# PSU2.net
KiCad netlist of a schematic drawn in Altium Designer
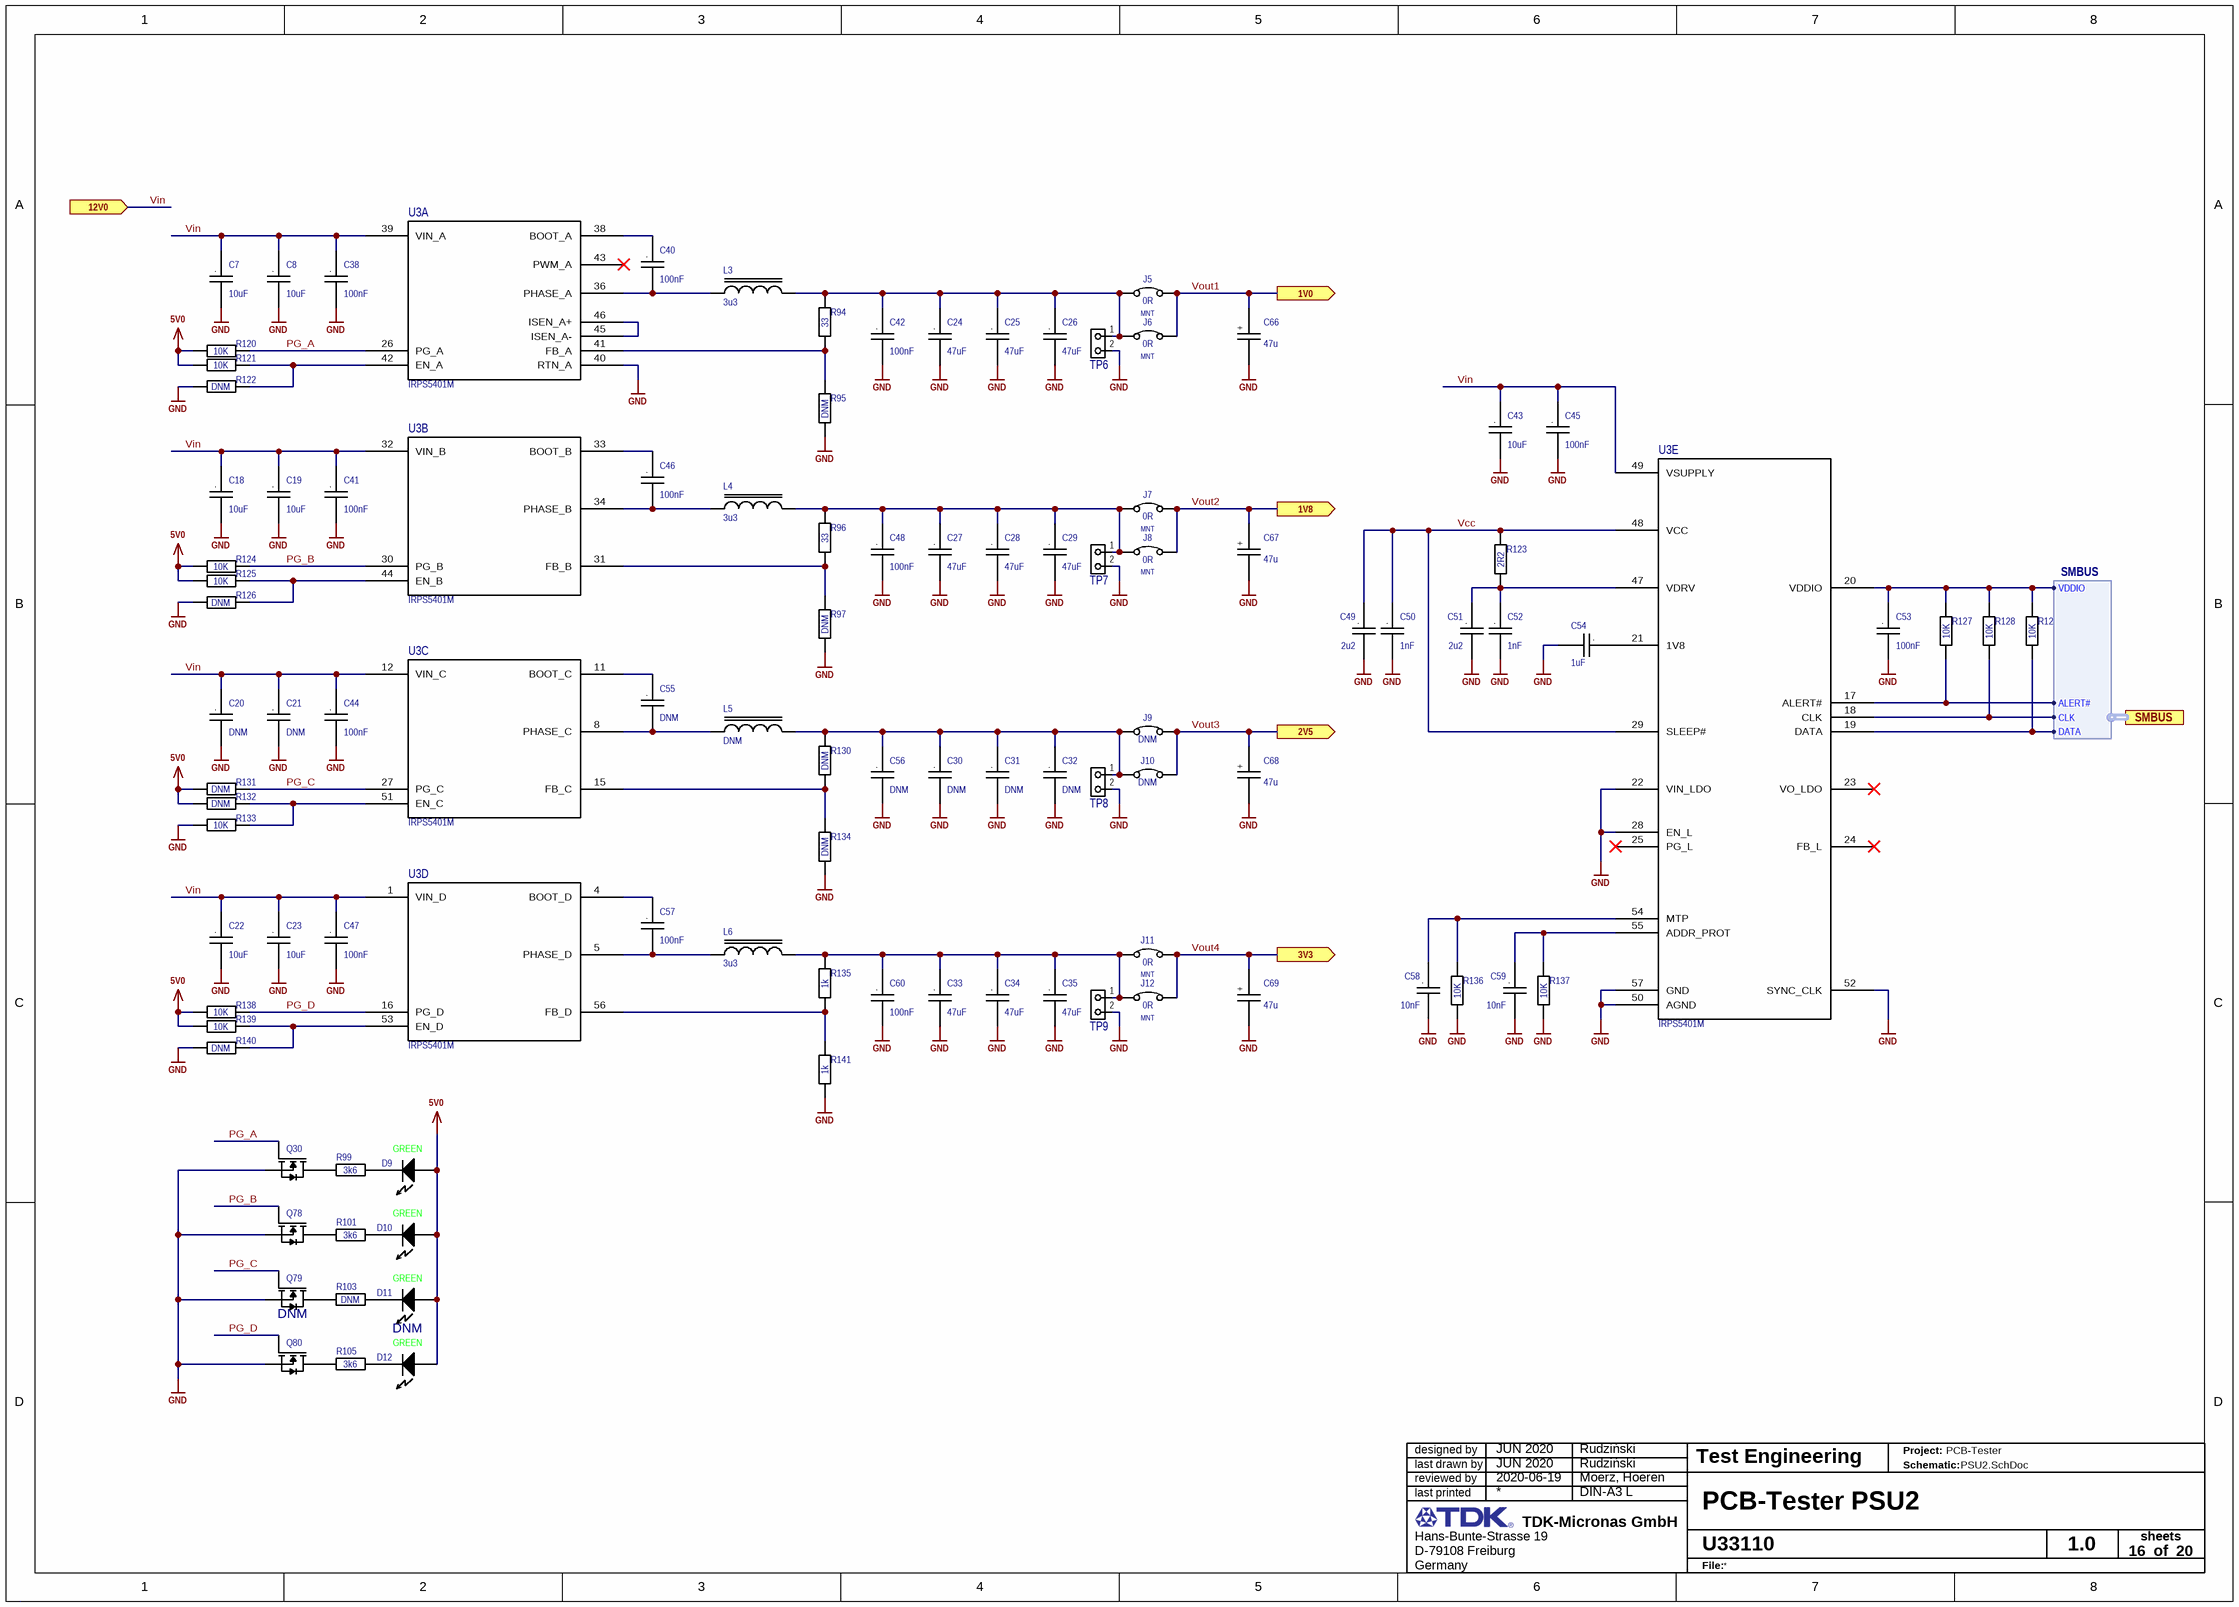
[diagram p0: PSU2.SchDoc]

(export (version "E")
  (design (tool "Eeschema 10.0.6"))
  (components
    (comp (ref "C7")
      (value "10uF")
      (footprint "C1206 Reflow")
      (description "CAP CER 10UF 25V X7R 1206")
      (fields (field (name "TOLERANCE") "±10%") (field (name "02. DISTRIBUTOR PART NUMBER") "445-7705-6-ND"))
      (libsource (lib "chickenfood") (part "C"))
    )
    (comp (ref "C8")
      (value "10uF")
      (footprint "C1206 Reflow")
      (description "CAP CER 10UF 25V X7R 1206")
      (fields (field (name "TOLERANCE") "±10%") (field (name "02. DISTRIBUTOR PART NUMBER") "445-7705-6-ND"))
      (libsource (lib "chickenfood") (part "C"))
    )
    (comp (ref "C18")
      (value "10uF")
      (footprint "C1206 Reflow")
      (description "CAP CER 10UF 25V X7R 1206")
      (fields (field (name "TOLERANCE") "±10%") (field (name "02. DISTRIBUTOR PART NUMBER") "445-7705-6-ND"))
      (libsource (lib "chickenfood") (part "C"))
    )
    (comp (ref "C19")
      (value "10uF")
      (footprint "C1206 Reflow")
      (description "CAP CER 10UF 25V X7R 1206")
      (fields (field (name "TOLERANCE") "±10%") (field (name "02. DISTRIBUTOR PART NUMBER") "445-7705-6-ND"))
      (libsource (lib "chickenfood") (part "C"))
    )
    (comp (ref "C20")
      (value "DNM")
      (footprint "C1206 Reflow")
      (description "CAP CER 10UF 25V X7R 1206")
      (fields (field (name "TOLERANCE") "±10%") (field (name "02. DISTRIBUTOR PART NUMBER") "445-7705-6-ND"))
      (libsource (lib "chickenfood") (part "C"))
    )
    (comp (ref "C21")
      (value "DNM")
      (footprint "C1206 Reflow")
      (description "CAP CER 10UF 25V X7R 1206")
      (fields (field (name "TOLERANCE") "±10%") (field (name "02. DISTRIBUTOR PART NUMBER") "445-7705-6-ND"))
      (libsource (lib "chickenfood") (part "C"))
    )
    (comp (ref "C22")
      (value "10uF")
      (footprint "C1206 Reflow")
      (description "CAP CER 10UF 25V X7R 1206")
      (fields (field (name "TOLERANCE") "±10%") (field (name "02. DISTRIBUTOR PART NUMBER") "445-7705-6-ND"))
      (libsource (lib "chickenfood") (part "C"))
    )
    (comp (ref "C23")
      (value "10uF")
      (footprint "C1206 Reflow")
      (description "CAP CER 10UF 25V X7R 1206")
      (fields (field (name "TOLERANCE") "±10%") (field (name "02. DISTRIBUTOR PART NUMBER") "445-7705-6-ND"))
      (libsource (lib "chickenfood") (part "C"))
    )
    (comp (ref "C24")
      (value "47uF")
      (footprint "C1210 Reflow")
      (description "CAP CER 47UF 10V X5R 1210")
      (fields (field (name "TOLERANCE") "±20%") (field (name "02. DISTRIBUTOR PART NUMBER") "1276-3380-6-ND"))
      (libsource (lib "chickenfood") (part "C"))
    )
    (comp (ref "C25")
      (value "47uF")
      (footprint "C1210 Reflow")
      (description "CAP CER 47UF 10V X5R 1210")
      (fields (field (name "TOLERANCE") "±20%") (field (name "02. DISTRIBUTOR PART NUMBER") "1276-3380-6-ND"))
      (libsource (lib "chickenfood") (part "C"))
    )
    (comp (ref "C26")
      (value "47uF")
      (footprint "C1210 Reflow")
      (description "CAP CER 47UF 10V X5R 1210")
      (fields (field (name "TOLERANCE") "±20%") (field (name "02. DISTRIBUTOR PART NUMBER") "1276-3380-6-ND"))
      (libsource (lib "chickenfood") (part "C"))
    )
    (comp (ref "C27")
      (value "47uF")
      (footprint "C1210 Reflow")
      (description "CAP CER 47UF 10V X5R 1210")
      (fields (field (name "TOLERANCE") "±20%") (field (name "02. DISTRIBUTOR PART NUMBER") "1276-3380-6-ND"))
      (libsource (lib "chickenfood") (part "C"))
    )
    (comp (ref "C28")
      (value "47uF")
      (footprint "C1210 Reflow")
      (description "CAP CER 47UF 10V X5R 1210")
      (fields (field (name "TOLERANCE") "±20%") (field (name "02. DISTRIBUTOR PART NUMBER") "1276-3380-6-ND"))
      (libsource (lib "chickenfood") (part "C"))
    )
    (comp (ref "C29")
      (value "47uF")
      (footprint "C1210 Reflow")
      (description "CAP CER 47UF 10V X5R 1210")
      (fields (field (name "TOLERANCE") "±20%") (field (name "02. DISTRIBUTOR PART NUMBER") "1276-3380-6-ND"))
      (libsource (lib "chickenfood") (part "C"))
    )
    (comp (ref "C30")
      (value "DNM")
      (footprint "C1210 Reflow")
      (description "CAP CER 47UF 10V X5R 1210")
      (fields (field (name "TOLERANCE") "±20%") (field (name "02. DISTRIBUTOR PART NUMBER") "1276-3380-6-ND"))
      (libsource (lib "chickenfood") (part "C"))
    )
    (comp (ref "C31")
      (value "DNM")
      (footprint "C1210 Reflow")
      (description "CAP CER 47UF 10V X5R 1210")
      (fields (field (name "TOLERANCE") "±20%") (field (name "02. DISTRIBUTOR PART NUMBER") "1276-3380-6-ND"))
      (libsource (lib "chickenfood") (part "C"))
    )
    (comp (ref "C32")
      (value "DNM")
      (footprint "C1210 Reflow")
      (description "CAP CER 47UF 10V X5R 1210")
      (fields (field (name "TOLERANCE") "±20%") (field (name "02. DISTRIBUTOR PART NUMBER") "1276-3380-6-ND"))
      (libsource (lib "chickenfood") (part "C"))
    )
    (comp (ref "C33")
      (value "47uF")
      (footprint "C1210 Reflow")
      (description "CAP CER 47UF 10V X5R 1210")
      (fields (field (name "TOLERANCE") "±20%") (field (name "02. DISTRIBUTOR PART NUMBER") "1276-3380-6-ND"))
      (libsource (lib "chickenfood") (part "C"))
    )
    (comp (ref "C34")
      (value "47uF")
      (footprint "C1210 Reflow")
      (description "CAP CER 47UF 10V X5R 1210")
      (fields (field (name "TOLERANCE") "±20%") (field (name "02. DISTRIBUTOR PART NUMBER") "1276-3380-6-ND"))
      (libsource (lib "chickenfood") (part "C"))
    )
    (comp (ref "C35")
      (value "47uF")
      (footprint "C1210 Reflow")
      (description "CAP CER 47UF 10V X5R 1210")
      (fields (field (name "TOLERANCE") "±20%") (field (name "02. DISTRIBUTOR PART NUMBER") "1276-3380-6-ND"))
      (libsource (lib "chickenfood") (part "C"))
    )
    (comp (ref "C38")
      (value "100nF")
      (footprint "C0402 Reflow")
      (description "CAP CER 0.1UF 25V X7R 0402")
      (fields (field (name "TOLERANCE") "±10%") (field (name "02. DISTRIBUTOR PART NUMBER") "311-2077-6-ND"))
      (libsource (lib "chickenfood") (part "C"))
    )
    (comp (ref "C40")
      (value "100nF")
      (footprint "C0402 Reflow")
      (description "CAP CER 0.1UF 25V X7R 0402")
      (fields (field (name "TOLERANCE") "±10%") (field (name "02. DISTRIBUTOR PART NUMBER") "311-2077-6-ND"))
      (libsource (lib "chickenfood") (part "C"))
    )
    (comp (ref "C41")
      (value "100nF")
      (footprint "C0402 Reflow")
      (description "CAP CER 0.1UF 25V X7R 0402")
      (fields (field (name "TOLERANCE") "±10%") (field (name "02. DISTRIBUTOR PART NUMBER") "311-2077-6-ND"))
      (libsource (lib "chickenfood") (part "C"))
    )
    (comp (ref "C42")
      (value "100nF")
      (footprint "C0402 Reflow")
      (description "CAP CER 0.1UF 25V X7R 0402")
      (fields (field (name "TOLERANCE") "±10%") (field (name "02. DISTRIBUTOR PART NUMBER") "311-2077-6-ND"))
      (libsource (lib "chickenfood") (part "C"))
    )
    (comp (ref "C43")
      (value "10uF")
      (footprint "C1206 Reflow")
      (description "CAP CER 10UF 25V X7R 1206")
      (fields (field (name "TOLERANCE") "±10%") (field (name "02. DISTRIBUTOR PART NUMBER") "445-7705-6-ND"))
      (libsource (lib "chickenfood") (part "C"))
    )
    (comp (ref "C44")
      (value "100nF")
      (footprint "C0402 Reflow")
      (description "CAP CER 0.1UF 25V X7R 0402")
      (fields (field (name "TOLERANCE") "±10%") (field (name "02. DISTRIBUTOR PART NUMBER") "311-2077-6-ND"))
      (libsource (lib "chickenfood") (part "C"))
    )
    (comp (ref "C45")
      (value "100nF")
      (footprint "C0402 Reflow")
      (description "CAP CER 0.1UF 25V X7R 0402")
      (fields (field (name "TOLERANCE") "±10%") (field (name "02. DISTRIBUTOR PART NUMBER") "311-2077-6-ND"))
      (libsource (lib "chickenfood") (part "C"))
    )
    (comp (ref "C46")
      (value "100nF")
      (footprint "C0402 Reflow")
      (description "CAP CER 0.1UF 25V X7R 0402")
      (fields (field (name "TOLERANCE") "±10%") (field (name "02. DISTRIBUTOR PART NUMBER") "311-2077-6-ND"))
      (libsource (lib "chickenfood") (part "C"))
    )
    (comp (ref "C47")
      (value "100nF")
      (footprint "C0402 Reflow")
      (description "CAP CER 0.1UF 25V X7R 0402")
      (fields (field (name "TOLERANCE") "±10%") (field (name "02. DISTRIBUTOR PART NUMBER") "311-2077-6-ND"))
      (libsource (lib "chickenfood") (part "C"))
    )
    (comp (ref "C48")
      (value "100nF")
      (footprint "C0402 Reflow")
      (description "CAP CER 0.1UF 25V X7R 0402")
      (fields (field (name "TOLERANCE") "±10%") (field (name "02. DISTRIBUTOR PART NUMBER") "311-2077-6-ND"))
      (libsource (lib "chickenfood") (part "C"))
    )
    (comp (ref "C49")
      (value "2u2")
      (footprint "C0805 Reflow")
      (description "CAP CER 2.2UF 10V X7R 0805")
      (fields
        (field (name "02. DISTRIBUTOR PART NUMBER") "1276-1188-1-ND")
        (field (name "07. MANUFACTURER  PART NUMBER") "CL21B225KPFNNNE")
      )
      (libsource (lib "PCB-Tester-Board-V1") (part "C_11"))
    )
    (comp (ref "C50")
      (value "1nF")
      (footprint "C0402 Reflow")
      (description "CAP CER 1000PF 25V X7R 0402")
      (fields (field (name "TOLERANCE") "±10%") (field (name "02. DISTRIBUTOR PART NUMBER") "399-1031-6-ND"))
      (libsource (lib "PCB-Tester-Board-V1") (part "C_7"))
    )
    (comp (ref "C51")
      (value "2u2")
      (footprint "C0805 Reflow")
      (description "CAP CER 2.2UF 10V X7R 0805")
      (fields
        (field (name "02. DISTRIBUTOR PART NUMBER") "1276-1188-1-ND")
        (field (name "07. MANUFACTURER  PART NUMBER") "CL21B225KPFNNNE")
      )
      (libsource (lib "PCB-Tester-Board-V1") (part "C_11"))
    )
    (comp (ref "C52")
      (value "1nF")
      (footprint "C0402 Reflow")
      (description "CAP CER 1000PF 25V X7R 0402")
      (fields (field (name "TOLERANCE") "±10%") (field (name "02. DISTRIBUTOR PART NUMBER") "399-1031-6-ND"))
      (libsource (lib "PCB-Tester-Board-V1") (part "C_7"))
    )
    (comp (ref "C53")
      (value "100nF")
      (footprint "C0402 Reflow")
      (description "CAP CER 0.1UF 25V X7R 0402")
      (fields (field (name "TOLERANCE") "±10%") (field (name "02. DISTRIBUTOR PART NUMBER") "311-2077-6-ND"))
      (libsource (lib "chickenfood") (part "C"))
    )
    (comp (ref "C54")
      (value "1uF")
      (footprint "C0402 Reflow")
      (description "CAP CER 1UF 6.3V X7R 0402")
      (fields (field (name "TOLERANCE") "±10%") (field (name "02. DISTRIBUTOR PART NUMBER") "490-13339-6-ND"))
      (libsource (lib "PCB-Tester-Board-V1") (part "C_2"))
    )
    (comp (ref "C55")
      (value "DNM")
      (footprint "C0402 Reflow")
      (description "CAP CER 0.1UF 25V X7R 0402")
      (fields (field (name "TOLERANCE") "±10%") (field (name "02. DISTRIBUTOR PART NUMBER") "311-2077-6-ND"))
      (libsource (lib "chickenfood") (part "C"))
    )
    (comp (ref "C56")
      (value "DNM")
      (footprint "C0402 Reflow")
      (description "CAP CER 0.1UF 25V X7R 0402")
      (fields (field (name "TOLERANCE") "±10%") (field (name "02. DISTRIBUTOR PART NUMBER") "311-2077-6-ND"))
      (libsource (lib "chickenfood") (part "C"))
    )
    (comp (ref "C57")
      (value "100nF")
      (footprint "C0402 Reflow")
      (description "CAP CER 0.1UF 25V X7R 0402")
      (fields (field (name "TOLERANCE") "±10%") (field (name "02. DISTRIBUTOR PART NUMBER") "311-2077-6-ND"))
      (libsource (lib "chickenfood") (part "C"))
    )
    (comp (ref "C58")
      (value "10nF")
      (footprint "C0402 Reflow")
      (description "CAP CER 0.01UF 25V X7R 0402")
      (fields (field (name "TOLERANCE") "±10%") (field (name "02. DISTRIBUTOR PART NUMBER") "490-6043-1-ND"))
      (libsource (lib "PCB-Tester-Board-V1") (part "C_10"))
    )
    (comp (ref "C59")
      (value "10nF")
      (footprint "C0402 Reflow")
      (description "CAP CER 0.01UF 25V X7R 0402")
      (fields (field (name "TOLERANCE") "±10%") (field (name "02. DISTRIBUTOR PART NUMBER") "490-6043-1-ND"))
      (libsource (lib "PCB-Tester-Board-V1") (part "C_10"))
    )
    (comp (ref "C60")
      (value "100nF")
      (footprint "C0402 Reflow")
      (description "CAP CER 0.1UF 25V X7R 0402")
      (fields (field (name "TOLERANCE") "±10%") (field (name "02. DISTRIBUTOR PART NUMBER") "311-2077-6-ND"))
      (libsource (lib "chickenfood") (part "C"))
    )
    (comp (ref "C66")
      (value "47u")
      (footprint "CAP_TAN_B")
      (description "CAP TANT 47UF 20% 10V 1411")
      (fields
        (field (name "02. DISTRIBUTOR PART NUMBER") "478-12531-1-ND")
        (field (name "07. MANUFACTURER  PART NUMBER") "F971A476MBAHT3")
      )
      (libsource (lib "PCB-Tester-Board-V1") (part "C+_TAN"))
    )
    (comp (ref "C67")
      (value "47u")
      (footprint "CAP_TAN_B")
      (description "CAP TANT 47UF 20% 10V 1411")
      (fields
        (field (name "02. DISTRIBUTOR PART NUMBER") "478-12531-1-ND")
        (field (name "07. MANUFACTURER  PART NUMBER") "F971A476MBAHT3")
      )
      (libsource (lib "PCB-Tester-Board-V1") (part "C+_TAN"))
    )
    (comp (ref "C68")
      (value "47u")
      (footprint "CAP_TAN_B")
      (description "CAP TANT 47UF 20% 10V 1411")
      (fields
        (field (name "02. DISTRIBUTOR PART NUMBER") "478-12531-1-ND")
        (field (name "07. MANUFACTURER  PART NUMBER") "F971A476MBAHT3")
      )
      (libsource (lib "PCB-Tester-Board-V1") (part "C+_TAN"))
    )
    (comp (ref "C69")
      (value "47u")
      (footprint "CAP_TAN_B")
      (description "CAP TANT 47UF 20% 10V 1411")
      (fields
        (field (name "02. DISTRIBUTOR PART NUMBER") "478-12531-1-ND")
        (field (name "07. MANUFACTURER  PART NUMBER") "F971A476MBAHT3")
      )
      (libsource (lib "PCB-Tester-Board-V1") (part "C+_TAN"))
    )
    (comp (ref "D9")
      (value "D")
      (footprint "L0603G")
      (description "LED GREEN DIFFUSED 0603 SMD")
      (fields
        (field (name "02. DISTRIBUTOR PART NUMBER") "475-2709-6-ND")
        (field (name "07. MANUFACTURER  PART NUMBER") "LG L29K-G2J1-24-Z")
        (field (name "COLOR") "GREEN")
      )
      (libsource (lib "chickenfood") (part "LED"))
    )
    (comp (ref "D10")
      (value "D")
      (footprint "L0603G")
      (description "LED GREEN DIFFUSED 0603 SMD")
      (fields
        (field (name "02. DISTRIBUTOR PART NUMBER") "475-2709-6-ND")
        (field (name "07. MANUFACTURER  PART NUMBER") "LG L29K-G2J1-24-Z")
        (field (name "COLOR") "GREEN")
      )
      (libsource (lib "chickenfood") (part "LED"))
    )
    (comp (ref "D11")
      (value "D")
      (footprint "L0603G")
      (description "LED GREEN DIFFUSED 0603 SMD")
      (fields
        (field (name "02. DISTRIBUTOR PART NUMBER") "475-2709-6-ND")
        (field (name "07. MANUFACTURER  PART NUMBER") "LG L29K-G2J1-24-Z")
        (field (name "COLOR") "GREEN")
        (field (name "NICNAME") "DNM")
      )
      (libsource (lib "chickenfood") (part "LED"))
    )
    (comp (ref "D12")
      (value "D")
      (footprint "L0603G")
      (description "LED GREEN DIFFUSED 0603 SMD")
      (fields
        (field (name "02. DISTRIBUTOR PART NUMBER") "475-2709-6-ND")
        (field (name "07. MANUFACTURER  PART NUMBER") "LG L29K-G2J1-24-Z")
        (field (name "COLOR") "GREEN")
      )
      (libsource (lib "chickenfood") (part "LED"))
    )
    (comp (ref "J5")
      (value "0R")
      (footprint "JumperSMD")
      (description "RES SMD 0 OHM JUMPER 1/10W 0603")
      (fields
        (field (name "02. DISTRIBUTOR PART NUMBER") "311-0.0GRDKR-ND")
        (field (name "07. MANUFACTURER  PART NUMBER") "RC0603JR-070RL")
        (field (name "POPULATED") "MNT")
      )
      (libsource (lib "chickenfood") (part "Jumper SMD"))
    )
    (comp (ref "J6")
      (value "0R")
      (footprint "JumperSMD")
      (description "RES SMD 0 OHM JUMPER 1/10W 0603")
      (fields
        (field (name "02. DISTRIBUTOR PART NUMBER") "311-0.0GRDKR-ND")
        (field (name "07. MANUFACTURER  PART NUMBER") "RC0603JR-070RL")
        (field (name "POPULATED") "MNT")
      )
      (libsource (lib "chickenfood") (part "Jumper SMD"))
    )
    (comp (ref "J7")
      (value "0R")
      (footprint "JumperSMD")
      (description "RES SMD 0 OHM JUMPER 1/10W 0603")
      (fields
        (field (name "02. DISTRIBUTOR PART NUMBER") "311-0.0GRDKR-ND")
        (field (name "07. MANUFACTURER  PART NUMBER") "RC0603JR-070RL")
        (field (name "POPULATED") "MNT")
      )
      (libsource (lib "chickenfood") (part "Jumper SMD"))
    )
    (comp (ref "J8")
      (value "0R")
      (footprint "JumperSMD")
      (description "RES SMD 0 OHM JUMPER 1/10W 0603")
      (fields
        (field (name "02. DISTRIBUTOR PART NUMBER") "311-0.0GRDKR-ND")
        (field (name "07. MANUFACTURER  PART NUMBER") "RC0603JR-070RL")
        (field (name "POPULATED") "MNT")
      )
      (libsource (lib "chickenfood") (part "Jumper SMD"))
    )
    (comp (ref "J9")
      (value "DNM")
      (footprint "JumperSMD")
      (description "RES SMD 0 OHM JUMPER 1/10W 0603")
      (fields
        (field (name "02. DISTRIBUTOR PART NUMBER") "311-0.0GRDKR-ND")
        (field (name "07. MANUFACTURER  PART NUMBER") "RC0603JR-070RL")
      )
      (libsource (lib "chickenfood") (part "Jumper SMD"))
    )
    (comp (ref "J10")
      (value "DNM")
      (footprint "JumperSMD")
      (description "RES SMD 0 OHM JUMPER 1/10W 0603")
      (fields
        (field (name "02. DISTRIBUTOR PART NUMBER") "311-0.0GRDKR-ND")
        (field (name "07. MANUFACTURER  PART NUMBER") "RC0603JR-070RL")
      )
      (libsource (lib "chickenfood") (part "Jumper SMD"))
    )
    (comp (ref "J11")
      (value "0R")
      (footprint "JumperSMD")
      (description "RES SMD 0 OHM JUMPER 1/10W 0603")
      (fields
        (field (name "02. DISTRIBUTOR PART NUMBER") "311-0.0GRDKR-ND")
        (field (name "07. MANUFACTURER  PART NUMBER") "RC0603JR-070RL")
        (field (name "POPULATED") "MNT")
      )
      (libsource (lib "chickenfood") (part "Jumper SMD"))
    )
    (comp (ref "J12")
      (value "0R")
      (footprint "JumperSMD")
      (description "RES SMD 0 OHM JUMPER 1/10W 0603")
      (fields
        (field (name "02. DISTRIBUTOR PART NUMBER") "311-0.0GRDKR-ND")
        (field (name "07. MANUFACTURER  PART NUMBER") "RC0603JR-070RL")
        (field (name "POPULATED") "MNT")
      )
      (libsource (lib "chickenfood") (part "Jumper SMD"))
    )
    (comp (ref "L3")
      (value "L")
      (footprint "XAL7070")
      (description "Fixed Inductors 3.3uH Shld 20% 15.1A 9.42mOhms AECQ2")
      (fields
        (field (name "02. DISTRIBUTOR PART NUMBER") "994-XAL7070-332MEC")
        (field (name "07. MANUFACTURER  PART NUMBER") "XAL7070-332MEC")
        (field (name "INDUCTANCE") "3u3")
      )
      (libsource (lib "PCB-Tester-Board-V1") (part "INDUCTOR"))
    )
    (comp (ref "L4")
      (value "L")
      (footprint "XAL7070")
      (description "Fixed Inductors 3.3uH Shld 20% 15.1A 9.42mOhms AECQ2")
      (fields
        (field (name "02. DISTRIBUTOR PART NUMBER") "994-XAL7070-332MEC")
        (field (name "07. MANUFACTURER  PART NUMBER") "XAL7070-332MEC")
        (field (name "INDUCTANCE") "3u3")
      )
      (libsource (lib "PCB-Tester-Board-V1") (part "INDUCTOR"))
    )
    (comp (ref "L5")
      (value "L")
      (footprint "XAL7070")
      (description "Fixed Inductors 3.3uH Shld 20% 15.1A 9.42mOhms AECQ2")
      (fields
        (field (name "02. DISTRIBUTOR PART NUMBER") "994-XAL7070-332MEC")
        (field (name "07. MANUFACTURER  PART NUMBER") "XAL7070-332MEC")
        (field (name "INDUCTANCE") "DNM")
      )
      (libsource (lib "PCB-Tester-Board-V1") (part "INDUCTOR"))
    )
    (comp (ref "L6")
      (value "L")
      (footprint "XAL7070")
      (description "Fixed Inductors 3.3uH Shld 20% 15.1A 9.42mOhms AECQ2")
      (fields
        (field (name "02. DISTRIBUTOR PART NUMBER") "994-XAL7070-332MEC")
        (field (name "07. MANUFACTURER  PART NUMBER") "XAL7070-332MEC")
        (field (name "INDUCTANCE") "3u3")
      )
      (libsource (lib "PCB-Tester-Board-V1") (part "INDUCTOR"))
    )
    (comp (ref "Q30")
      (value "Q")
      (footprint "SOT23-3")
      (description "MOSFET N-CH 25V 680MA SOT-23")
      (fields
        (field (name "02. DISTRIBUTOR PART NUMBER") "FDV303NDKR-ND")
        (field (name "07. MANUFACTURER  PART NUMBER") "FDV303N")
      )
      (libsource (lib "PCB-Tester-Board-V1") (part "FDV303N"))
    )
    (comp (ref "Q78")
      (value "Q")
      (footprint "SOT23-3")
      (description "MOSFET N-CH 25V 680MA SOT-23")
      (fields
        (field (name "02. DISTRIBUTOR PART NUMBER") "FDV303NDKR-ND")
        (field (name "07. MANUFACTURER  PART NUMBER") "FDV303N")
      )
      (libsource (lib "PCB-Tester-Board-V1") (part "FDV303N"))
    )
    (comp (ref "Q79")
      (value "Q")
      (footprint "SOT23-3")
      (description "MOSFET N-CH 25V 680MA SOT-23")
      (fields
        (field (name "02. DISTRIBUTOR PART NUMBER") "FDV303NDKR-ND")
        (field (name "07. MANUFACTURER  PART NUMBER") "FDV303N")
        (field (name "NICNAME") "DNM")
      )
      (libsource (lib "PCB-Tester-Board-V1") (part "FDV303N"))
    )
    (comp (ref "Q80")
      (value "Q")
      (footprint "SOT23-3")
      (description "MOSFET N-CH 25V 680MA SOT-23")
      (fields
        (field (name "02. DISTRIBUTOR PART NUMBER") "FDV303NDKR-ND")
        (field (name "07. MANUFACTURER  PART NUMBER") "FDV303N")
      )
      (libsource (lib "PCB-Tester-Board-V1") (part "FDV303N"))
    )
    (comp (ref "R94")
      (value "33")
      (footprint "R0402 Reflow")
      (description "RES SMD 33 OHM 1% 1/16W 0402")
      (fields
        (field (name "TOLERANCE") "±1%")
        (field (name "02. DISTRIBUTOR PART NUMBER") "311-33.0LRDKR-ND")
      )
      (libsource (lib "chickenfood") (part "R"))
    )
    (comp (ref "R95")
      (value "DNM")
      (footprint "R0402 Reflow")
      (description "RES SMD 10K OHM 1% 1/16W 0402")
      (fields
        (field (name "TOLERANCE") "±1%")
        (field (name "02. DISTRIBUTOR PART NUMBER") "311-10.0KLRDKR-ND")
      )
      (libsource (lib "chickenfood") (part "R"))
    )
    (comp (ref "R96")
      (value "33")
      (footprint "R0402 Reflow")
      (description "RES SMD 33 OHM 1% 1/16W 0402")
      (fields
        (field (name "TOLERANCE") "±1%")
        (field (name "02. DISTRIBUTOR PART NUMBER") "311-33.0LRDKR-ND")
      )
      (libsource (lib "chickenfood") (part "R"))
    )
    (comp (ref "R97")
      (value "DNM")
      (footprint "R0402 Reflow")
      (description "RES SMD 10K OHM 1% 1/16W 0402")
      (fields
        (field (name "TOLERANCE") "±1%")
        (field (name "02. DISTRIBUTOR PART NUMBER") "311-10.0KLRDKR-ND")
      )
      (libsource (lib "chickenfood") (part "R"))
    )
    (comp (ref "R99")
      (value "3k6")
      (footprint "R0603 Reflow")
      (description "RES SMD 3.6K OHM 1% 1/10W 0603")
      (fields
        (field (name "TOLERANCE") "±1%")
        (field (name "02. DISTRIBUTOR PART NUMBER") "311-3.60KHRCT-ND")
      )
      (libsource (lib "") (part "R_2"))
    )
    (comp (ref "R101")
      (value "3k6")
      (footprint "R0603 Reflow")
      (description "RES SMD 3.6K OHM 1% 1/10W 0603")
      (fields
        (field (name "TOLERANCE") "±1%")
        (field (name "02. DISTRIBUTOR PART NUMBER") "311-3.60KHRCT-ND")
      )
      (libsource (lib "") (part "R_2"))
    )
    (comp (ref "R103")
      (value "DNM")
      (footprint "R0603 Reflow")
      (description "RES SMD 1.65K OHM 1% 1/16W 0402")
      (fields (field (name "TOLERANCE") "±1%") (field (name "02. DISTRIBUTOR PART NUMBER") "YAG3043DKR-ND"))
      (libsource (lib "") (part "R_2"))
    )
    (comp (ref "R105")
      (value "3k6")
      (footprint "R0603 Reflow")
      (description "RES SMD 3.6K OHM 1% 1/10W 0603")
      (fields
        (field (name "TOLERANCE") "±1%")
        (field (name "02. DISTRIBUTOR PART NUMBER") "311-3.60KHRCT-ND")
      )
      (libsource (lib "") (part "R_2"))
    )
    (comp (ref "R120")
      (value "10K")
      (footprint "R0402 Reflow")
      (description "RES SMD 10K OHM 1% 1/16W 0402")
      (fields
        (field (name "TOLERANCE") "±1%")
        (field (name "02. DISTRIBUTOR PART NUMBER") "311-10.0KLRDKR-ND")
      )
      (libsource (lib "") (part "R_1"))
    )
    (comp (ref "R121")
      (value "10K")
      (footprint "R0402 Reflow")
      (description "RES SMD 10K OHM 1% 1/16W 0402")
      (fields
        (field (name "TOLERANCE") "±1%")
        (field (name "02. DISTRIBUTOR PART NUMBER") "311-10.0KLRDKR-ND")
      )
      (libsource (lib "") (part "R_1"))
    )
    (comp (ref "R122")
      (value "DNM")
      (footprint "R0402 Reflow")
      (description "RES SMD 10K OHM 1% 1/16W 0402")
      (fields
        (field (name "TOLERANCE") "±1%")
        (field (name "02. DISTRIBUTOR PART NUMBER") "311-10.0KLRDKR-ND")
      )
      (libsource (lib "") (part "R_1"))
    )
    (comp (ref "R123")
      (value "2R2")
      (footprint "R0402 Reflow")
      (description "RES SMD 2.2 OHM 1% 1/16W 0402")
      (fields (field (name "TOLERANCE") "±1%") (field (name "02. DISTRIBUTOR PART NUMBER") "311-2.20LRTR-ND"))
      (libsource (lib "PCB-Tester-Board-V1") (part "R_24"))
    )
    (comp (ref "R124")
      (value "10K")
      (footprint "R0402 Reflow")
      (description "RES SMD 10K OHM 1% 1/16W 0402")
      (fields
        (field (name "TOLERANCE") "±1%")
        (field (name "02. DISTRIBUTOR PART NUMBER") "311-10.0KLRDKR-ND")
      )
      (libsource (lib "") (part "R_1"))
    )
    (comp (ref "R125")
      (value "10K")
      (footprint "R0402 Reflow")
      (description "RES SMD 10K OHM 1% 1/16W 0402")
      (fields
        (field (name "TOLERANCE") "±1%")
        (field (name "02. DISTRIBUTOR PART NUMBER") "311-10.0KLRDKR-ND")
      )
      (libsource (lib "") (part "R_1"))
    )
    (comp (ref "R126")
      (value "DNM")
      (footprint "R0402 Reflow")
      (description "RES SMD 10K OHM 1% 1/16W 0402")
      (fields
        (field (name "TOLERANCE") "±1%")
        (field (name "02. DISTRIBUTOR PART NUMBER") "311-10.0KLRDKR-ND")
      )
      (libsource (lib "") (part "R_1"))
    )
    (comp (ref "R127")
      (value "10K")
      (footprint "R0402 Reflow")
      (description "RES SMD 10K OHM 1% 1/16W 0402")
      (fields
        (field (name "TOLERANCE") "±1%")
        (field (name "02. DISTRIBUTOR PART NUMBER") "311-10.0KLRDKR-ND")
      )
      (libsource (lib "chickenfood") (part "R"))
    )
    (comp (ref "R128")
      (value "10K")
      (footprint "R0402 Reflow")
      (description "RES SMD 10K OHM 1% 1/16W 0402")
      (fields
        (field (name "TOLERANCE") "±1%")
        (field (name "02. DISTRIBUTOR PART NUMBER") "311-10.0KLRDKR-ND")
      )
      (libsource (lib "chickenfood") (part "R"))
    )
    (comp (ref "R129")
      (value "10K")
      (footprint "R0402 Reflow")
      (description "RES SMD 10K OHM 1% 1/16W 0402")
      (fields
        (field (name "TOLERANCE") "±1%")
        (field (name "02. DISTRIBUTOR PART NUMBER") "311-10.0KLRDKR-ND")
      )
      (libsource (lib "chickenfood") (part "R"))
    )
    (comp (ref "R130")
      (value "DNM")
      (footprint "R0402 Reflow")
      (description "RES SMD 10K OHM 1% 1/16W 0402")
      (fields
        (field (name "TOLERANCE") "±1%")
        (field (name "02. DISTRIBUTOR PART NUMBER") "311-10.0KLRDKR-ND")
      )
      (libsource (lib "chickenfood") (part "R"))
    )
    (comp (ref "R131")
      (value "DNM")
      (footprint "R0402 Reflow")
      (description "RES SMD 10K OHM 1% 1/16W 0402")
      (fields
        (field (name "TOLERANCE") "±1%")
        (field (name "02. DISTRIBUTOR PART NUMBER") "311-10.0KLRDKR-ND")
      )
      (libsource (lib "") (part "R_1"))
    )
    (comp (ref "R132")
      (value "DNM")
      (footprint "R0402 Reflow")
      (description "RES SMD 10K OHM 1% 1/16W 0402")
      (fields
        (field (name "TOLERANCE") "±1%")
        (field (name "02. DISTRIBUTOR PART NUMBER") "311-10.0KLRDKR-ND")
      )
      (libsource (lib "") (part "R_1"))
    )
    (comp (ref "R133")
      (value "10K")
      (footprint "R0402 Reflow")
      (description "RES SMD 10K OHM 1% 1/16W 0402")
      (fields
        (field (name "TOLERANCE") "±1%")
        (field (name "02. DISTRIBUTOR PART NUMBER") "311-10.0KLRDKR-ND")
      )
      (libsource (lib "") (part "R_1"))
    )
    (comp (ref "R134")
      (value "DNM")
      (footprint "R0402 Reflow")
      (description "RES SMD 10K OHM 1% 1/16W 0402")
      (fields
        (field (name "TOLERANCE") "±1%")
        (field (name "02. DISTRIBUTOR PART NUMBER") "311-10.0KLRDKR-ND")
      )
      (libsource (lib "chickenfood") (part "R"))
    )
    (comp (ref "R135")
      (value "1k")
      (footprint "R0402 Reflow")
      (description "RES SMD 1K OHM 1% 1/16W 0402")
      (fields (field (name "TOLERANCE") "±1%") (field (name "02. DISTRIBUTOR PART NUMBER") "YAG1254CT-ND"))
      (libsource (lib "chickenfood") (part "R"))
    )
    (comp (ref "R136")
      (value "10K")
      (footprint "R0402 Reflow")
      (description "RES SMD 10K OHM 1% 1/16W 0402")
      (fields
        (field (name "TOLERANCE") "±1%")
        (field (name "02. DISTRIBUTOR PART NUMBER") "311-10.0KLRDKR-ND")
      )
      (libsource (lib "chickenfood") (part "R"))
    )
    (comp (ref "R137")
      (value "10K")
      (footprint "R0402 Reflow")
      (description "RES SMD 10K OHM 1% 1/16W 0402")
      (fields
        (field (name "TOLERANCE") "±1%")
        (field (name "02. DISTRIBUTOR PART NUMBER") "311-10.0KLRDKR-ND")
      )
      (libsource (lib "chickenfood") (part "R"))
    )
    (comp (ref "R138")
      (value "10K")
      (footprint "R0402 Reflow")
      (description "RES SMD 10K OHM 1% 1/16W 0402")
      (fields
        (field (name "TOLERANCE") "±1%")
        (field (name "02. DISTRIBUTOR PART NUMBER") "311-10.0KLRDKR-ND")
      )
      (libsource (lib "") (part "R_1"))
    )
    (comp (ref "R139")
      (value "10K")
      (footprint "R0402 Reflow")
      (description "RES SMD 10K OHM 1% 1/16W 0402")
      (fields
        (field (name "TOLERANCE") "±1%")
        (field (name "02. DISTRIBUTOR PART NUMBER") "311-10.0KLRDKR-ND")
      )
      (libsource (lib "") (part "R_1"))
    )
    (comp (ref "R140")
      (value "DNM")
      (footprint "R0402 Reflow")
      (description "RES SMD 10K OHM 1% 1/16W 0402")
      (fields
        (field (name "TOLERANCE") "±1%")
        (field (name "02. DISTRIBUTOR PART NUMBER") "311-10.0KLRDKR-ND")
      )
      (libsource (lib "") (part "R_1"))
    )
    (comp (ref "R141")
      (value "1k")
      (footprint "R0402 Reflow")
      (description "RES SMD 1K OHM 1% 1/16W 0402")
      (fields (field (name "TOLERANCE") "±1%") (field (name "02. DISTRIBUTOR PART NUMBER") "YAG1254CT-ND"))
      (libsource (lib "chickenfood") (part "R"))
    )
    (comp (ref "TP6")
      (value "TP")
      (footprint "DualTestpoint 100mils")
      (description "Dual testpoint, pitch 2.54mm")
      (fields (field (name "02. DISTRIBUTOR PART NUMBER") "HMTSW-103-07-G-S-240"))
      (libsource (lib "PCB-Tester-Board-V1") (part "DualTestpoint 100mils"))
    )
    (comp (ref "TP7")
      (value "TP")
      (footprint "DualTestpoint 100mils")
      (description "Dual testpoint, pitch 2.54mm")
      (fields (field (name "02. DISTRIBUTOR PART NUMBER") "HMTSW-103-07-G-S-240"))
      (libsource (lib "PCB-Tester-Board-V1") (part "DualTestpoint 100mils"))
    )
    (comp (ref "TP8")
      (value "TP")
      (footprint "DualTestpoint 100mils")
      (description "Dual testpoint, pitch 2.54mm")
      (fields (field (name "02. DISTRIBUTOR PART NUMBER") "HMTSW-103-07-G-S-240"))
      (libsource (lib "PCB-Tester-Board-V1") (part "DualTestpoint 100mils"))
    )
    (comp (ref "TP9")
      (value "TP")
      (footprint "DualTestpoint 100mils")
      (description "Dual testpoint, pitch 2.54mm")
      (fields (field (name "02. DISTRIBUTOR PART NUMBER") "HMTSW-103-07-G-S-240"))
      (libsource (lib "PCB-Tester-Board-V1") (part "DualTestpoint 100mils"))
    )
    (comp (ref "U3")
      (value "IRPS5401M")
      (footprint "QFN4-7x7-56_IRPS5401M")
      (description "POL - SUPIRBUCK")
      (fields
        (field (name "MFR") "Infineon")
        (field (name "07. MANUFACTURER  PART NUMBER") "IRPS5401MTRPBF")
        (field (name "NICNAME") "IRPS5401M")
      )
      (libsource (lib "PCB-Tester-Board-V1") (part "IRPS5401M"))
    )
  )
  (nets
    (net (code "2") (name "/PG_A") (class "Default")
      (node (ref "Q30") (pin "1") (pinfunction "G_1") (pintype "passive"))
      (node (ref "R120") (pin "1") (pinfunction "1_1") (pintype "passive"))
      (node (ref "U3") (pin "26") (pinfunction "PG_A_26") (pintype "passive"))
    )
    (net (code "3") (name "/PG_B") (class "Default")
      (node (ref "Q78") (pin "1") (pinfunction "G_1") (pintype "passive"))
      (node (ref "R124") (pin "1") (pinfunction "1_1") (pintype "passive"))
      (node (ref "U3") (pin "30") (pinfunction "PG_B_30") (pintype "passive"))
    )
    (net (code "4") (name "/PG_C") (class "Default")
      (node (ref "Q79") (pin "1") (pinfunction "G_1") (pintype "passive"))
      (node (ref "R131") (pin "1") (pinfunction "1_1") (pintype "passive"))
      (node (ref "U3") (pin "27") (pinfunction "PG_C_27") (pintype "passive"))
    )
    (net (code "5") (name "/PG_D") (class "Default")
      (node (ref "Q80") (pin "1") (pinfunction "G_1") (pintype "passive"))
      (node (ref "R138") (pin "1") (pinfunction "1_1") (pintype "passive"))
      (node (ref "U3") (pin "16") (pinfunction "PG_D_16") (pintype "passive"))
    )
    (net (code "6") (name "/Vcc") (class "Default")
      (node (ref "C49") (pin "1") (pinfunction "1_1") (pintype "passive"))
      (node (ref "C50") (pin "1") (pinfunction "1_1") (pintype "passive"))
      (node (ref "R123") (pin "2") (pinfunction "2_2") (pintype "passive"))
      (node (ref "U3") (pin "29") (pinfunction "SLEEP#_29") (pintype "passive"))
      (node (ref "U3") (pin "48") (pinfunction "VCC_48") (pintype "passive"))
    )
    (net (code "7") (name "/Vin") (class "Default")
      (node (ref "C18") (pin "1") (pinfunction "1_1") (pintype "passive"))
      (node (ref "C19") (pin "1") (pinfunction "1_1") (pintype "passive"))
      (node (ref "C20") (pin "1") (pinfunction "1_1") (pintype "passive"))
      (node (ref "C21") (pin "1") (pinfunction "1_1") (pintype "passive"))
      (node (ref "C22") (pin "1") (pinfunction "1_1") (pintype "passive"))
      (node (ref "C23") (pin "1") (pinfunction "1_1") (pintype "passive"))
      (node (ref "C38") (pin "1") (pinfunction "1_1") (pintype "passive"))
      (node (ref "C41") (pin "1") (pinfunction "1_1") (pintype "passive"))
      (node (ref "C43") (pin "1") (pinfunction "1_1") (pintype "passive"))
      (node (ref "C44") (pin "1") (pinfunction "1_1") (pintype "passive"))
      (node (ref "C45") (pin "1") (pinfunction "1_1") (pintype "passive"))
      (node (ref "C47") (pin "1") (pinfunction "1_1") (pintype "passive"))
      (node (ref "C7") (pin "1") (pinfunction "1_1") (pintype "passive"))
      (node (ref "C8") (pin "1") (pinfunction "1_1") (pintype "passive"))
      (node (ref "U3") (pin "1") (pinfunction "VIN_D_1") (pintype "passive"))
      (node (ref "U3") (pin "12") (pinfunction "VIN_C_12") (pintype "passive"))
      (node (ref "U3") (pin "32") (pinfunction "VIN_B_32") (pintype "passive"))
      (node (ref "U3") (pin "39") (pinfunction "VIN_A_39") (pintype "passive"))
      (node (ref "U3") (pin "49") (pinfunction "VSUPPLY_49") (pintype "passive"))
    )
    (net (code "8") (name "/Vout1") (class "Default")
      (node (ref "C66") (pin "1") (pinfunction "1_1") (pintype "passive"))
      (node (ref "J5") (pin "2") (pinfunction "2_2") (pintype "passive"))
      (node (ref "J6") (pin "2") (pinfunction "2_2") (pintype "passive"))
    )
    (net (code "9") (name "/Vout2") (class "Default")
      (node (ref "C67") (pin "1") (pinfunction "1_1") (pintype "passive"))
      (node (ref "J7") (pin "2") (pinfunction "2_2") (pintype "passive"))
      (node (ref "J8") (pin "2") (pinfunction "2_2") (pintype "passive"))
    )
    (net (code "10") (name "/Vout3") (class "Default")
      (node (ref "C68") (pin "1") (pinfunction "1_1") (pintype "passive"))
      (node (ref "J10") (pin "2") (pinfunction "2_2") (pintype "passive"))
      (node (ref "J9") (pin "2") (pinfunction "2_2") (pintype "passive"))
    )
    (net (code "11") (name "/Vout4") (class "Default")
      (node (ref "C69") (pin "1") (pinfunction "1_1") (pintype "passive"))
      (node (ref "J11") (pin "2") (pinfunction "2_2") (pintype "passive"))
      (node (ref "J12") (pin "2") (pinfunction "2_2") (pintype "passive"))
    )
    (net (code "13") (name "5V0") (class "Default")
      (node (ref "D10") (pin "1") (pinfunction "Anode_1") (pintype "passive"))
      (node (ref "D11") (pin "1") (pinfunction "Anode_1") (pintype "passive"))
      (node (ref "D12") (pin "1") (pinfunction "Anode_1") (pintype "passive"))
      (node (ref "D9") (pin "1") (pinfunction "Anode_1") (pintype "passive"))
      (node (ref "R120") (pin "2") (pinfunction "2_2") (pintype "passive"))
      (node (ref "R121") (pin "2") (pinfunction "2_2") (pintype "passive"))
      (node (ref "R124") (pin "2") (pinfunction "2_2") (pintype "passive"))
      (node (ref "R125") (pin "2") (pinfunction "2_2") (pintype "passive"))
      (node (ref "R131") (pin "2") (pinfunction "2_2") (pintype "passive"))
      (node (ref "R132") (pin "2") (pinfunction "2_2") (pintype "passive"))
      (node (ref "R138") (pin "2") (pinfunction "2_2") (pintype "passive"))
      (node (ref "R139") (pin "2") (pinfunction "2_2") (pintype "passive"))
    )
    (net (code "14") (name "GND") (class "Default")
      (node (ref "C18") (pin "2") (pinfunction "2_2") (pintype "passive"))
      (node (ref "C19") (pin "2") (pinfunction "2_2") (pintype "passive"))
      (node (ref "C20") (pin "2") (pinfunction "2_2") (pintype "passive"))
      (node (ref "C21") (pin "2") (pinfunction "2_2") (pintype "passive"))
      (node (ref "C22") (pin "2") (pinfunction "2_2") (pintype "passive"))
      (node (ref "C23") (pin "2") (pinfunction "2_2") (pintype "passive"))
      (node (ref "C24") (pin "2") (pinfunction "2_2") (pintype "passive"))
      (node (ref "C25") (pin "2") (pinfunction "2_2") (pintype "passive"))
      (node (ref "C26") (pin "2") (pinfunction "2_2") (pintype "passive"))
      (node (ref "C27") (pin "2") (pinfunction "2_2") (pintype "passive"))
      (node (ref "C28") (pin "2") (pinfunction "2_2") (pintype "passive"))
      (node (ref "C29") (pin "2") (pinfunction "2_2") (pintype "passive"))
      (node (ref "C30") (pin "2") (pinfunction "2_2") (pintype "passive"))
      (node (ref "C31") (pin "2") (pinfunction "2_2") (pintype "passive"))
      (node (ref "C32") (pin "2") (pinfunction "2_2") (pintype "passive"))
      (node (ref "C33") (pin "2") (pinfunction "2_2") (pintype "passive"))
      (node (ref "C34") (pin "2") (pinfunction "2_2") (pintype "passive"))
      (node (ref "C35") (pin "2") (pinfunction "2_2") (pintype "passive"))
      (node (ref "C38") (pin "2") (pinfunction "2_2") (pintype "passive"))
      (node (ref "C41") (pin "2") (pinfunction "2_2") (pintype "passive"))
      (node (ref "C42") (pin "2") (pinfunction "2_2") (pintype "passive"))
      (node (ref "C43") (pin "2") (pinfunction "2_2") (pintype "passive"))
      (node (ref "C44") (pin "2") (pinfunction "2_2") (pintype "passive"))
      (node (ref "C45") (pin "2") (pinfunction "2_2") (pintype "passive"))
      (node (ref "C47") (pin "2") (pinfunction "2_2") (pintype "passive"))
      (node (ref "C48") (pin "2") (pinfunction "2_2") (pintype "passive"))
      (node (ref "C49") (pin "2") (pinfunction "2_2") (pintype "passive"))
      (node (ref "C50") (pin "2") (pinfunction "2_2") (pintype "passive"))
      (node (ref "C51") (pin "2") (pinfunction "2_2") (pintype "passive"))
      (node (ref "C52") (pin "2") (pinfunction "2_2") (pintype "passive"))
      (node (ref "C53") (pin "2") (pinfunction "2_2") (pintype "passive"))
      (node (ref "C54") (pin "2") (pinfunction "2_2") (pintype "passive"))
      (node (ref "C56") (pin "2") (pinfunction "2_2") (pintype "passive"))
      (node (ref "C58") (pin "2") (pinfunction "2_2") (pintype "passive"))
      (node (ref "C59") (pin "2") (pinfunction "2_2") (pintype "passive"))
      (node (ref "C60") (pin "2") (pinfunction "2_2") (pintype "passive"))
      (node (ref "C66") (pin "2") (pinfunction "2_2") (pintype "passive"))
      (node (ref "C67") (pin "2") (pinfunction "2_2") (pintype "passive"))
      (node (ref "C68") (pin "2") (pinfunction "2_2") (pintype "passive"))
      (node (ref "C69") (pin "2") (pinfunction "2_2") (pintype "passive"))
      (node (ref "C7") (pin "2") (pinfunction "2_2") (pintype "passive"))
      (node (ref "C8") (pin "2") (pinfunction "2_2") (pintype "passive"))
      (node (ref "Q30") (pin "2") (pinfunction "S_2") (pintype "passive"))
      (node (ref "Q78") (pin "2") (pinfunction "S_2") (pintype "passive"))
      (node (ref "Q79") (pin "2") (pinfunction "S_2") (pintype "passive"))
      (node (ref "Q80") (pin "2") (pinfunction "S_2") (pintype "passive"))
      (node (ref "R122") (pin "2") (pinfunction "2_2") (pintype "passive"))
      (node (ref "R126") (pin "2") (pinfunction "2_2") (pintype "passive"))
      (node (ref "R133") (pin "2") (pinfunction "2_2") (pintype "passive"))
      (node (ref "R134") (pin "1") (pinfunction "1_1") (pintype "passive"))
      (node (ref "R136") (pin "1") (pinfunction "1_1") (pintype "passive"))
      (node (ref "R137") (pin "1") (pinfunction "1_1") (pintype "passive"))
      (node (ref "R140") (pin "2") (pinfunction "2_2") (pintype "passive"))
      (node (ref "R141") (pin "1") (pinfunction "1_1") (pintype "passive"))
      (node (ref "R95") (pin "1") (pinfunction "1_1") (pintype "passive"))
      (node (ref "R97") (pin "1") (pinfunction "1_1") (pintype "passive"))
      (node (ref "TP6") (pin "2") (pinfunction "2_2") (pintype "passive"))
      (node (ref "TP7") (pin "2") (pinfunction "2_2") (pintype "passive"))
      (node (ref "TP8") (pin "2") (pinfunction "2_2") (pintype "passive"))
      (node (ref "TP9") (pin "2") (pinfunction "2_2") (pintype "passive"))
      (node (ref "U3") (pin "22") (pinfunction "VIN_LDO_22") (pintype "passive"))
      (node (ref "U3") (pin "28") (pinfunction "EN_L_28") (pintype "passive"))
      (node (ref "U3") (pin "40") (pinfunction "RTN_A_40") (pintype "passive"))
      (node (ref "U3") (pin "50") (pinfunction "AGND_50") (pintype "passive"))
      (node (ref "U3") (pin "52") (pinfunction "SYNC_CLK_52") (pintype "passive"))
      (node (ref "U3") (pin "57") (pinfunction "GND_57") (pintype "passive"))
    )
    (net (code "15") (name "Net-(C24-Pad1)") (class "Default")
      (node (ref "C24") (pin "1") (pinfunction "1_1") (pintype "passive"))
      (node (ref "C25") (pin "1") (pinfunction "1_1") (pintype "passive"))
      (node (ref "C26") (pin "1") (pinfunction "1_1") (pintype "passive"))
      (node (ref "C42") (pin "1") (pinfunction "1_1") (pintype "passive"))
      (node (ref "J5") (pin "1") (pinfunction "1_1") (pintype "passive"))
      (node (ref "J6") (pin "1") (pinfunction "1_1") (pintype "passive"))
      (node (ref "L3") (pin "2") (pinfunction "2_2") (pintype "passive"))
      (node (ref "R94") (pin "2") (pinfunction "2_2") (pintype "passive"))
      (node (ref "TP6") (pin "1") (pinfunction "1_1") (pintype "passive"))
    )
    (net (code "16") (name "Net-(C27-Pad1)") (class "Default")
      (node (ref "C27") (pin "1") (pinfunction "1_1") (pintype "passive"))
      (node (ref "C28") (pin "1") (pinfunction "1_1") (pintype "passive"))
      (node (ref "C29") (pin "1") (pinfunction "1_1") (pintype "passive"))
      (node (ref "C48") (pin "1") (pinfunction "1_1") (pintype "passive"))
      (node (ref "J7") (pin "1") (pinfunction "1_1") (pintype "passive"))
      (node (ref "J8") (pin "1") (pinfunction "1_1") (pintype "passive"))
      (node (ref "L4") (pin "2") (pinfunction "2_2") (pintype "passive"))
      (node (ref "R96") (pin "2") (pinfunction "2_2") (pintype "passive"))
      (node (ref "TP7") (pin "1") (pinfunction "1_1") (pintype "passive"))
    )
    (net (code "17") (name "Net-(C30-Pad1)") (class "Default")
      (node (ref "C30") (pin "1") (pinfunction "1_1") (pintype "passive"))
      (node (ref "C31") (pin "1") (pinfunction "1_1") (pintype "passive"))
      (node (ref "C32") (pin "1") (pinfunction "1_1") (pintype "passive"))
      (node (ref "C56") (pin "1") (pinfunction "1_1") (pintype "passive"))
      (node (ref "J10") (pin "1") (pinfunction "1_1") (pintype "passive"))
      (node (ref "J9") (pin "1") (pinfunction "1_1") (pintype "passive"))
      (node (ref "L5") (pin "2") (pinfunction "2_2") (pintype "passive"))
      (node (ref "R130") (pin "2") (pinfunction "2_2") (pintype "passive"))
      (node (ref "TP8") (pin "1") (pinfunction "1_1") (pintype "passive"))
    )
    (net (code "18") (name "Net-(C33-Pad1)") (class "Default")
      (node (ref "C33") (pin "1") (pinfunction "1_1") (pintype "passive"))
      (node (ref "C34") (pin "1") (pinfunction "1_1") (pintype "passive"))
      (node (ref "C35") (pin "1") (pinfunction "1_1") (pintype "passive"))
      (node (ref "C60") (pin "1") (pinfunction "1_1") (pintype "passive"))
      (node (ref "J11") (pin "1") (pinfunction "1_1") (pintype "passive"))
      (node (ref "J12") (pin "1") (pinfunction "1_1") (pintype "passive"))
      (node (ref "L6") (pin "2") (pinfunction "2_2") (pintype "passive"))
      (node (ref "R135") (pin "2") (pinfunction "2_2") (pintype "passive"))
      (node (ref "TP9") (pin "1") (pinfunction "1_1") (pintype "passive"))
    )
    (net (code "19") (name "Net-(D9-Cathode)") (class "Default")
      (node (ref "D9") (pin "2") (pinfunction "Cathode_2") (pintype "passive"))
      (node (ref "R99") (pin "2") (pinfunction "2_2") (pintype "passive"))
    )
    (net (code "20") (name "Net-(D10-Cathode)") (class "Default")
      (node (ref "D10") (pin "2") (pinfunction "Cathode_2") (pintype "passive"))
      (node (ref "R101") (pin "2") (pinfunction "2_2") (pintype "passive"))
    )
    (net (code "21") (name "Net-(D11-Cathode)") (class "Default")
      (node (ref "D11") (pin "2") (pinfunction "Cathode_2") (pintype "passive"))
      (node (ref "R103") (pin "2") (pinfunction "2_2") (pintype "passive"))
    )
    (net (code "22") (name "Net-(D12-Cathode)") (class "Default")
      (node (ref "D12") (pin "2") (pinfunction "Cathode_2") (pintype "passive"))
      (node (ref "R105") (pin "2") (pinfunction "2_2") (pintype "passive"))
    )
    (net (code "23") (name "Net-(Q30-D)") (class "Default")
      (node (ref "Q30") (pin "3") (pinfunction "D_3") (pintype "passive"))
      (node (ref "R99") (pin "1") (pinfunction "1_1") (pintype "passive"))
    )
    (net (code "24") (name "Net-(Q78-D)") (class "Default")
      (node (ref "Q78") (pin "3") (pinfunction "D_3") (pintype "passive"))
      (node (ref "R101") (pin "1") (pinfunction "1_1") (pintype "passive"))
    )
    (net (code "25") (name "Net-(Q79-D)") (class "Default")
      (node (ref "Q79") (pin "3") (pinfunction "D_3") (pintype "passive"))
      (node (ref "R103") (pin "1") (pinfunction "1_1") (pintype "passive"))
    )
    (net (code "26") (name "Net-(Q80-D)") (class "Default")
      (node (ref "Q80") (pin "3") (pinfunction "D_3") (pintype "passive"))
      (node (ref "R105") (pin "1") (pinfunction "1_1") (pintype "passive"))
    )
    (net (code "27") (name "Net-(U3A-BOOT_A)") (class "Default")
      (node (ref "C40") (pin "1") (pinfunction "1_1") (pintype "passive"))
      (node (ref "U3") (pin "38") (pinfunction "BOOT_A_38") (pintype "passive"))
    )
    (net (code "28") (name "Net-(U3A-EN_A)") (class "Default")
      (node (ref "R121") (pin "1") (pinfunction "1_1") (pintype "passive"))
      (node (ref "R122") (pin "1") (pinfunction "1_1") (pintype "passive"))
      (node (ref "U3") (pin "42") (pinfunction "EN_A_42") (pintype "passive"))
    )
    (net (code "29") (name "Net-(U3A-FB_A)") (class "Default")
      (node (ref "R94") (pin "1") (pinfunction "1_1") (pintype "passive"))
      (node (ref "R95") (pin "2") (pinfunction "2_2") (pintype "passive"))
      (node (ref "U3") (pin "41") (pinfunction "FB_A_41") (pintype "passive"))
    )
    (net (code "30") (name "Net-(U3A-ISEN_A+)") (class "Default")
      (node (ref "U3") (pin "45") (pinfunction "ISEN_A-_45") (pintype "passive"))
      (node (ref "U3") (pin "46") (pinfunction "ISEN_A+_46") (pintype "passive"))
    )
    (net (code "31") (name "Net-(U3A-PHASE_A)") (class "Default")
      (node (ref "C40") (pin "2") (pinfunction "2_2") (pintype "passive"))
      (node (ref "L3") (pin "1") (pinfunction "1_1") (pintype "passive"))
      (node (ref "U3") (pin "36") (pinfunction "PHASE_A_36") (pintype "passive"))
    )
    (net (code "32") (name "Net-(U3B-BOOT_B)") (class "Default")
      (node (ref "C46") (pin "1") (pinfunction "1_1") (pintype "passive"))
      (node (ref "U3") (pin "33") (pinfunction "BOOT_B_33") (pintype "passive"))
    )
    (net (code "33") (name "Net-(U3B-EN_B)") (class "Default")
      (node (ref "R125") (pin "1") (pinfunction "1_1") (pintype "passive"))
      (node (ref "R126") (pin "1") (pinfunction "1_1") (pintype "passive"))
      (node (ref "U3") (pin "44") (pinfunction "EN_B_44") (pintype "passive"))
    )
    (net (code "34") (name "Net-(U3B-FB_B)") (class "Default")
      (node (ref "R96") (pin "1") (pinfunction "1_1") (pintype "passive"))
      (node (ref "R97") (pin "2") (pinfunction "2_2") (pintype "passive"))
      (node (ref "U3") (pin "31") (pinfunction "FB_B_31") (pintype "passive"))
    )
    (net (code "35") (name "Net-(U3B-PHASE_B)") (class "Default")
      (node (ref "C46") (pin "2") (pinfunction "2_2") (pintype "passive"))
      (node (ref "L4") (pin "1") (pinfunction "1_1") (pintype "passive"))
      (node (ref "U3") (pin "34") (pinfunction "PHASE_B_34") (pintype "passive"))
    )
    (net (code "36") (name "Net-(U3C-BOOT_C)") (class "Default")
      (node (ref "C55") (pin "1") (pinfunction "1_1") (pintype "passive"))
      (node (ref "U3") (pin "11") (pinfunction "BOOT_C_11") (pintype "passive"))
    )
    (net (code "37") (name "Net-(U3C-EN_C)") (class "Default")
      (node (ref "R132") (pin "1") (pinfunction "1_1") (pintype "passive"))
      (node (ref "R133") (pin "1") (pinfunction "1_1") (pintype "passive"))
      (node (ref "U3") (pin "51") (pinfunction "EN_C_51") (pintype "passive"))
    )
    (net (code "38") (name "Net-(U3C-FB_C)") (class "Default")
      (node (ref "R130") (pin "1") (pinfunction "1_1") (pintype "passive"))
      (node (ref "R134") (pin "2") (pinfunction "2_2") (pintype "passive"))
      (node (ref "U3") (pin "15") (pinfunction "FB_C_15") (pintype "passive"))
    )
    (net (code "39") (name "Net-(U3C-PHASE_C)") (class "Default")
      (node (ref "C55") (pin "2") (pinfunction "2_2") (pintype "passive"))
      (node (ref "L5") (pin "1") (pinfunction "1_1") (pintype "passive"))
      (node (ref "U3") (pin "8") (pinfunction "PHASE_C_8") (pintype "passive"))
    )
    (net (code "40") (name "Net-(U3D-BOOT_D)") (class "Default")
      (node (ref "C57") (pin "1") (pinfunction "1_1") (pintype "passive"))
      (node (ref "U3") (pin "4") (pinfunction "BOOT_D_4") (pintype "passive"))
    )
    (net (code "41") (name "Net-(U3D-EN_D)") (class "Default")
      (node (ref "R139") (pin "1") (pinfunction "1_1") (pintype "passive"))
      (node (ref "R140") (pin "1") (pinfunction "1_1") (pintype "passive"))
      (node (ref "U3") (pin "53") (pinfunction "EN_D_53") (pintype "passive"))
    )
    (net (code "42") (name "Net-(U3D-FB_D)") (class "Default")
      (node (ref "R135") (pin "1") (pinfunction "1_1") (pintype "passive"))
      (node (ref "R141") (pin "2") (pinfunction "2_2") (pintype "passive"))
      (node (ref "U3") (pin "56") (pinfunction "FB_D_56") (pintype "passive"))
    )
    (net (code "43") (name "Net-(U3D-PHASE_D)") (class "Default")
      (node (ref "C57") (pin "2") (pinfunction "2_2") (pintype "passive"))
      (node (ref "L6") (pin "1") (pinfunction "1_1") (pintype "passive"))
      (node (ref "U3") (pin "5") (pinfunction "PHASE_D_5") (pintype "passive"))
    )
    (net (code "44") (name "Net-(U3E-1V8)") (class "Default")
      (node (ref "C54") (pin "1") (pinfunction "1_1") (pintype "passive"))
      (node (ref "U3") (pin "21") (pinfunction "1V8_21") (pintype "passive"))
    )
    (net (code "45") (name "Net-(U3E-ADDR_PROT)") (class "Default")
      (node (ref "C59") (pin "1") (pinfunction "1_1") (pintype "passive"))
      (node (ref "R137") (pin "2") (pinfunction "2_2") (pintype "passive"))
      (node (ref "U3") (pin "55") (pinfunction "ADDR_PROT_55") (pintype "passive"))
    )
    (net (code "46") (name "Net-(U3E-ALERT#)") (class "Default")
      (node (ref "R127") (pin "1") (pinfunction "1_1") (pintype "passive"))
      (node (ref "U3") (pin "17") (pinfunction "ALERT#_17") (pintype "passive"))
    )
    (net (code "47") (name "Net-(U3E-CLK)") (class "Default")
      (node (ref "R128") (pin "1") (pinfunction "1_1") (pintype "passive"))
      (node (ref "U3") (pin "18") (pinfunction "CLK_18") (pintype "passive"))
    )
    (net (code "48") (name "Net-(U3E-DATA)") (class "Default")
      (node (ref "R129") (pin "1") (pinfunction "1_1") (pintype "passive"))
      (node (ref "U3") (pin "19") (pinfunction "DATA_19") (pintype "passive"))
    )
    (net (code "49") (name "Net-(U3E-MTP)") (class "Default")
      (node (ref "C58") (pin "1") (pinfunction "1_1") (pintype "passive"))
      (node (ref "R136") (pin "2") (pinfunction "2_2") (pintype "passive"))
      (node (ref "U3") (pin "54") (pinfunction "MTP_54") (pintype "passive"))
    )
    (net (code "50") (name "Net-(U3E-VDDIO)") (class "Default")
      (node (ref "C53") (pin "1") (pinfunction "1_1") (pintype "passive"))
      (node (ref "R127") (pin "2") (pinfunction "2_2") (pintype "passive"))
      (node (ref "R128") (pin "2") (pinfunction "2_2") (pintype "passive"))
      (node (ref "R129") (pin "2") (pinfunction "2_2") (pintype "passive"))
      (node (ref "U3") (pin "20") (pinfunction "VDDIO_20") (pintype "passive"))
    )
    (net (code "51") (name "Net-(U3E-VDRV)") (class "Default")
      (node (ref "C51") (pin "1") (pinfunction "1_1") (pintype "passive"))
      (node (ref "C52") (pin "1") (pinfunction "1_1") (pintype "passive"))
      (node (ref "R123") (pin "1") (pinfunction "1_1") (pintype "passive"))
      (node (ref "U3") (pin "47") (pinfunction "VDRV_47") (pintype "passive"))
    )
    (net (code "52") (name "unconnected-(U3A-PWM_A-Pad43)") (class "Default")
      (node (ref "U3") (pin "43") (pinfunction "PWM_A_43") (pintype "passive+no_connect"))
    )
    (net (code "53") (name "unconnected-(U3E-FB_L-Pad24)") (class "Default")
      (node (ref "U3") (pin "24") (pinfunction "FB_L_24") (pintype "passive+no_connect"))
    )
    (net (code "54") (name "unconnected-(U3E-PG_L-Pad25)") (class "Default")
      (node (ref "U3") (pin "25") (pinfunction "PG_L_25") (pintype "passive+no_connect"))
    )
    (net (code "55") (name "unconnected-(U3E-VO_LDO-Pad23)") (class "Default")
      (node (ref "U3") (pin "23") (pinfunction "VO_LDO_23") (pintype "passive+no_connect"))
    )
  )
)
